# TP1.net
KiCad netlist of a schematic drawn in EAGLE
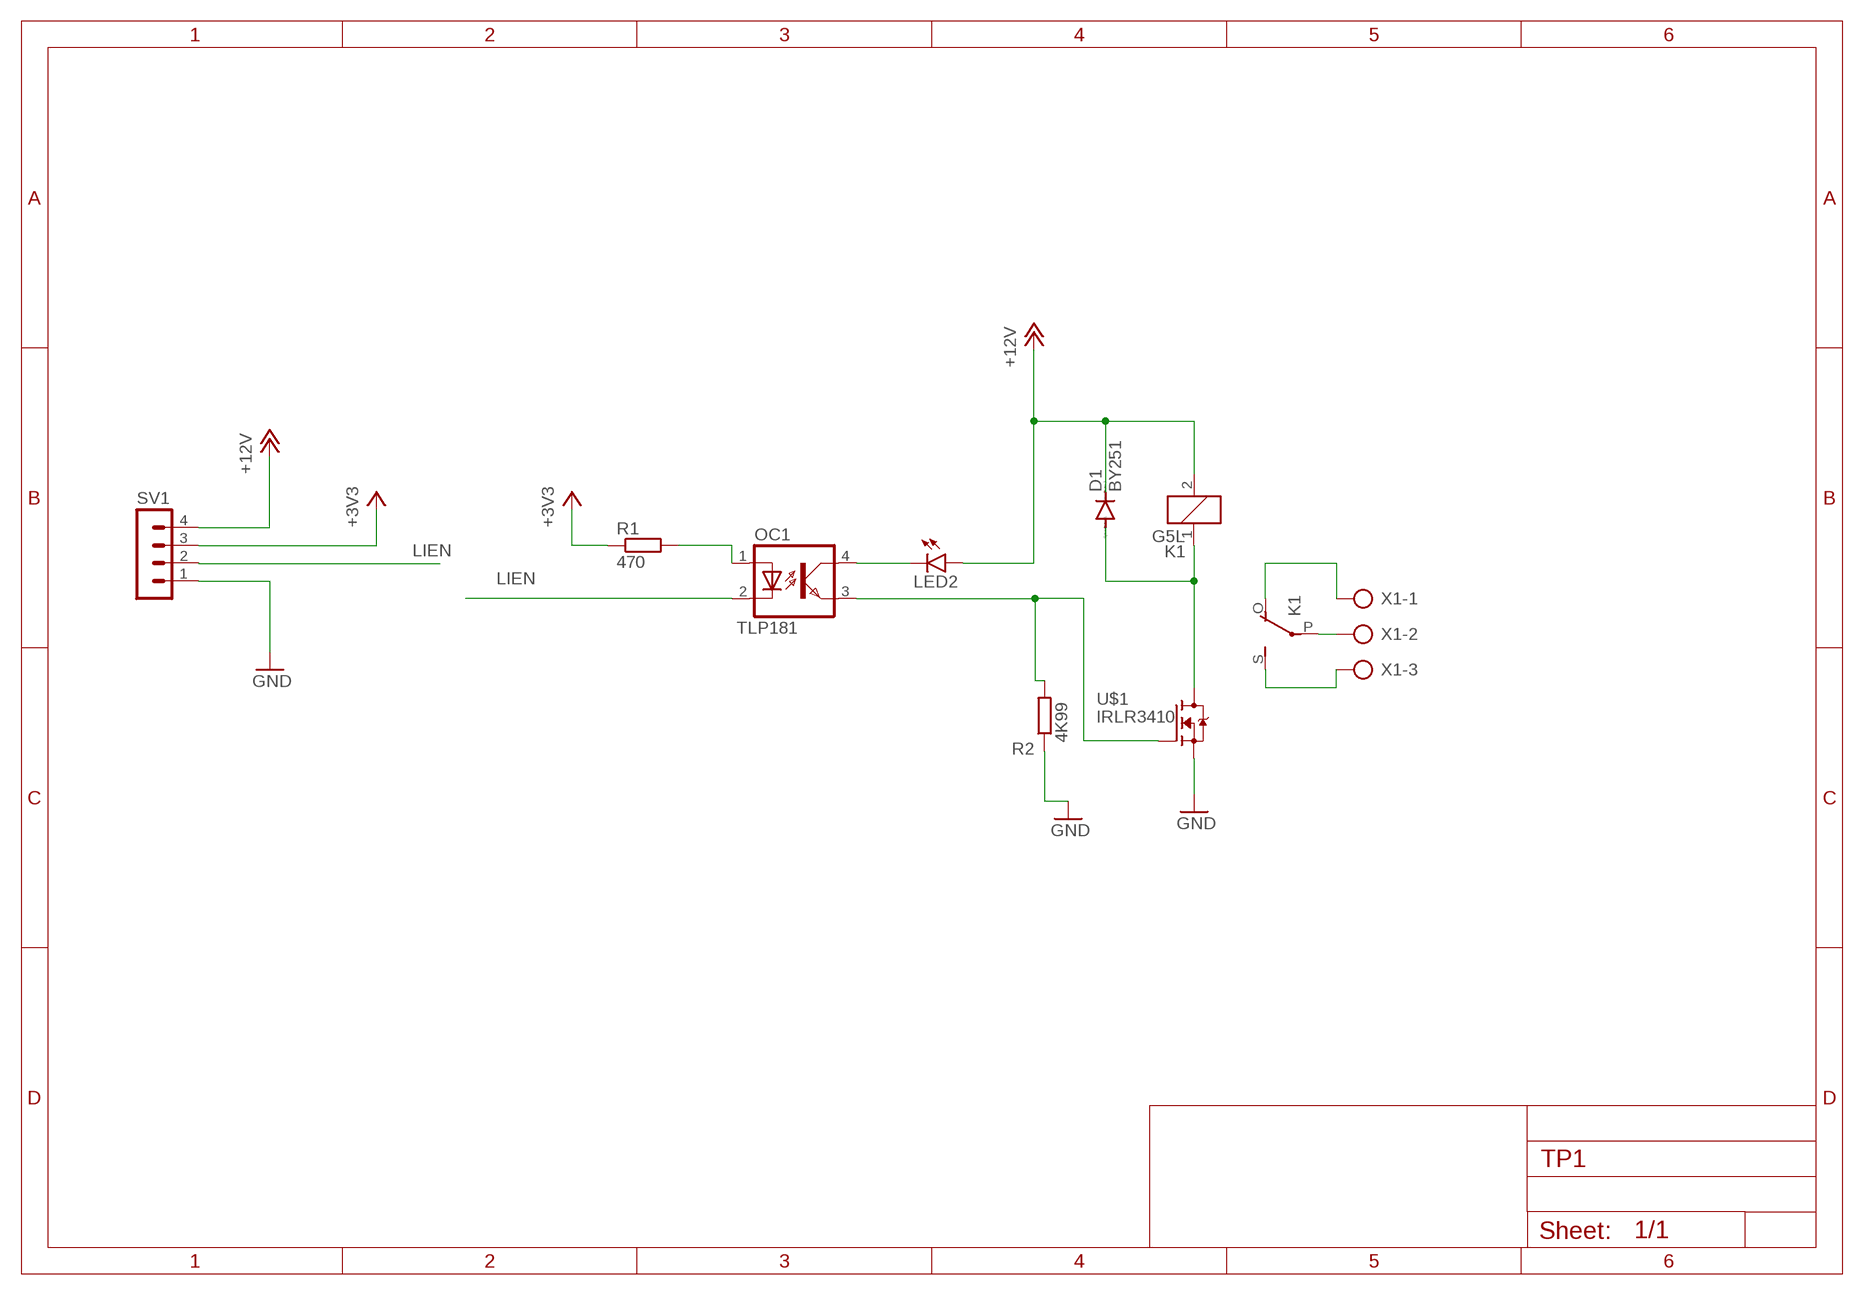
[diagram p0: schematic, sheet 1]

(export (version "E")
  (design (tool "Eeschema 10.0.6"))
  (components
    (comp (ref "D1")
      (value "BY251")
      (footprint "eagle-import:DO201-15")
      (libsource (lib "eagle-import") (part "BY251"))
    )
    (comp (ref "K1")
      (value "G5L")
      (footprint "eagle-import:G5LE")
      (libsource (lib "eagle-import") (part "G5L"))
    )
    (comp (ref "LED2")
      (value "LED3MM")
      (footprint "eagle-import:LED3MM")
      (libsource (lib "eagle-import") (part "LED3MM"))
    )
    (comp (ref "OC1")
      (value "TLP181")
      (footprint "eagle-import:SO-4")
      (libsource (lib "eagle-import") (part "TLP181"))
    )
    (comp (ref "R1")
      (value "470")
      (footprint "eagle-import:R1206")
      (libsource (lib "eagle-import") (part "R-EU_R1206"))
    )
    (comp (ref "R2")
      (value "4K99")
      (footprint "eagle-import:R1206")
      (libsource (lib "eagle-import") (part "R-EU_R1206"))
    )
    (comp (ref "SV1")
      (value "MA04-1")
      (footprint "eagle-import:MA04-1")
      (libsource (lib "eagle-import") (part "MA04-1"))
    )
    (comp (ref "U$1")
      (value "IRLR3410")
      (footprint "eagle-import:TO252")
      (libsource (lib "eagle-import") (part "IRLR3410"))
    )
    (comp (ref "X1")
      (value "AK300/3")
      (footprint "eagle-import:AK300_3")
      (libsource (lib "eagle-import") (part "AK300/3"))
    )
  )
  (nets
    (net (code "1") (name "+3V3") (class "Default")
      (node (ref "R1") (pin "1") (pinfunction "1_1") (pintype "passive"))
      (node (ref "SV1") (pin "3") (pinfunction "3_3") (pintype "passive"))
    )
    (net (code "2") (name "+12V") (class "Default")
      (node (ref "D1") (pin "C") (pinfunction "C_C") (pintype "passive"))
      (node (ref "K1") (pin "2") (pinfunction "2_2") (pintype "passive"))
      (node (ref "LED2") (pin "A") (pinfunction "A_A") (pintype "passive"))
      (node (ref "SV1") (pin "4") (pinfunction "4_4") (pintype "passive"))
    )
    (net (code "3") (name "/LIEN") (class "Default")
      (node (ref "OC1") (pin "2") (pinfunction "C_2") (pintype "passive"))
      (node (ref "SV1") (pin "2") (pinfunction "2_2") (pintype "passive"))
    )
    (net (code "4") (name "GND") (class "Default")
      (node (ref "R2") (pin "1") (pinfunction "1_1") (pintype "passive"))
      (node (ref "SV1") (pin "1") (pinfunction "1_1") (pintype "passive"))
      (node (ref "U$1") (pin "3") (pinfunction "S_3") (pintype "passive"))
    )
    (net (code "5") (name "Net-(LED2-C)") (class "Default")
      (node (ref "LED2") (pin "K") (pinfunction "C_K") (pintype "passive"))
      (node (ref "OC1") (pin "4") (pinfunction "COL_4") (pintype "passive"))
    )
    (net (code "6") (name "Net-(OC1-A)") (class "Default")
      (node (ref "OC1") (pin "1") (pinfunction "A_1") (pintype "passive"))
      (node (ref "R1") (pin "2") (pinfunction "2_2") (pintype "passive"))
    )
    (net (code "7") (name "Net-(OC1-EMIT)") (class "Default")
      (node (ref "OC1") (pin "3") (pinfunction "EMIT_3") (pintype "passive"))
      (node (ref "R2") (pin "2") (pinfunction "2_2") (pintype "passive"))
      (node (ref "U$1") (pin "1") (pinfunction "G_1") (pintype "passive"))
    )
    (net (code "8") (name "Net-(U$1-D)") (class "Default")
      (node (ref "D1") (pin "A") (pinfunction "A_A") (pintype "passive"))
      (node (ref "K1") (pin "1") (pinfunction "1_1") (pintype "passive"))
      (node (ref "U$1") (pin "4") (pinfunction "D_4") (pintype "passive"))
    )
    (net (code "9") (name "Net-(X1A-KL)") (class "Default")
      (node (ref "K1") (pin "O") (pinfunction "O_O") (pintype "passive"))
      (node (ref "X1") (pin "1") (pinfunction "KL_1") (pintype "passive"))
    )
    (net (code "10") (name "Net-(X1B-KL)") (class "Default")
      (node (ref "K1") (pin "P") (pinfunction "P_P") (pintype "passive"))
      (node (ref "X1") (pin "2") (pinfunction "KL_2") (pintype "passive"))
    )
    (net (code "11") (name "Net-(X1C-KL)") (class "Default")
      (node (ref "K1") (pin "S") (pinfunction "S_S") (pintype "passive"))
      (node (ref "X1") (pin "3") (pinfunction "KL_3") (pintype "passive"))
    )
  )
)
